# protections_1.net
KiCad netlist of a schematic drawn in Altium Designer
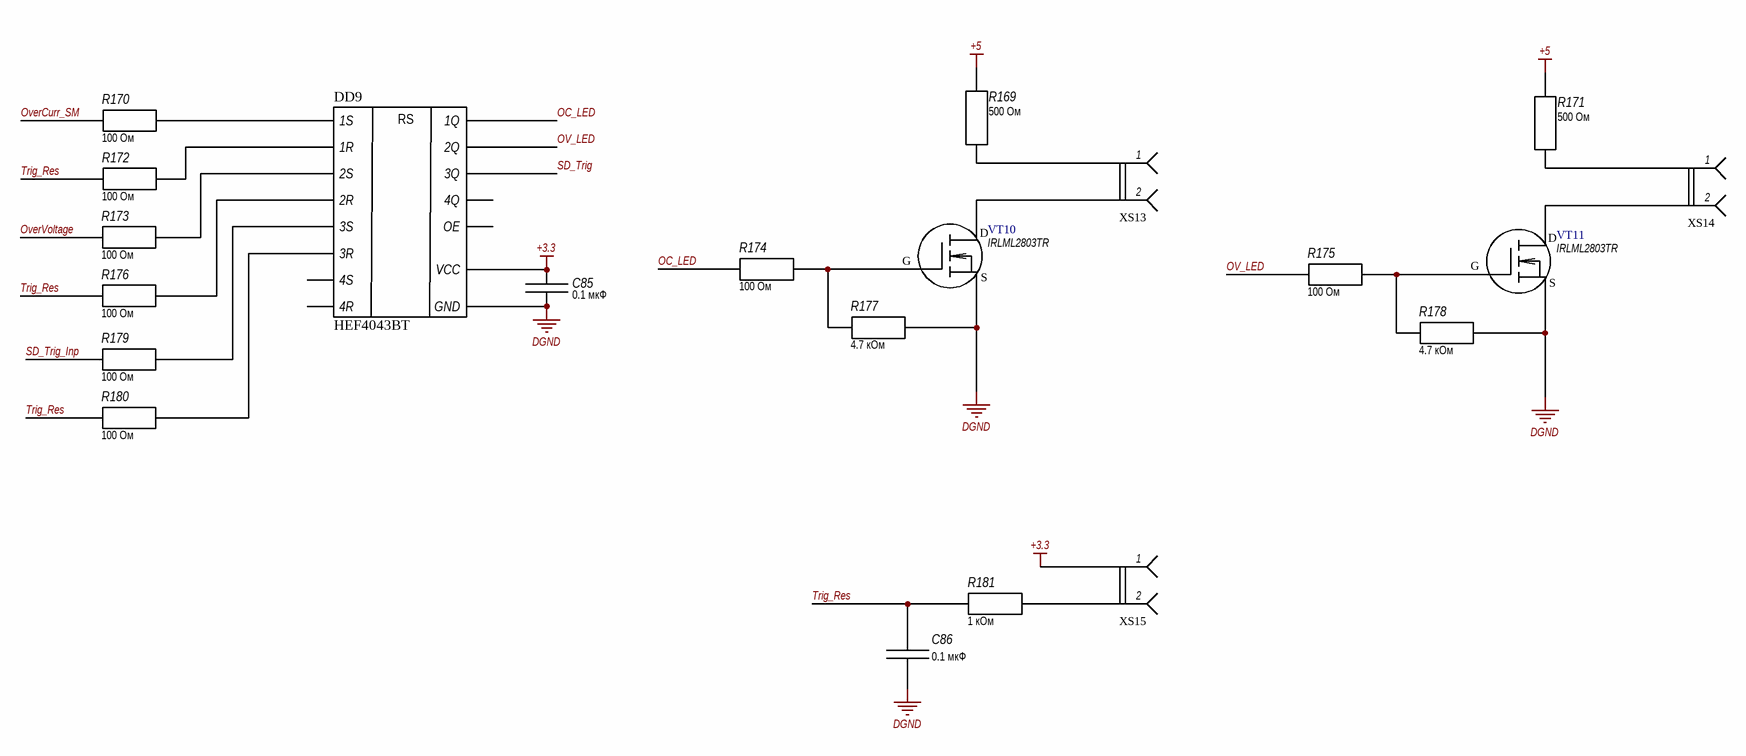
[diagram p0: protections_1.SchDoc]

(export (version "E")
  (design (tool "Eeschema 10.0.6"))
  (components
    (comp (ref "C85")
      (value "0.1 мкФ")
      (footprint "CC0603")
      (fields (field (name "VOLTAGE") "16В") (field (name "Comment") "Capacitor"))
      (libsource (lib "Main_components") (part "Capacitor"))
    )
    (comp (ref "C86")
      (value "0.1 мкФ")
      (footprint "CC0603")
      (fields (field (name "VOLTAGE") "50 В") (field (name "Comment") "Capacitor"))
      (libsource (lib "Main_components") (part "Capacitor"))
    )
    (comp (ref "DD9")
      (value "HEF4043BT")
      (footprint "SO16")
      (description "Триггер RS-типа х 4 [SOIC-16]")
      (libsource (lib "Microcircuits") (part "HEF4043BT"))
    )
    (comp (ref "R169")
      (value "500 Ом")
      (footprint "RC1206")
      (fields (field (name "POWER") "250 мВт") (field (name "Comment") "Resistor"))
      (libsource (lib "Main_components") (part "Resistor"))
    )
    (comp (ref "R170")
      (value "100 Ом")
      (footprint "RC0603")
      (fields (field (name "POWER") "100 мВт") (field (name "Comment") "Resistor"))
      (libsource (lib "Main_components") (part "Resistor"))
    )
    (comp (ref "R171")
      (value "500 Ом")
      (footprint "RC1206")
      (fields (field (name "POWER") "250 мВт") (field (name "Comment") "Resistor"))
      (libsource (lib "Main_components") (part "Resistor"))
    )
    (comp (ref "R172")
      (value "100 Ом")
      (footprint "RC0603")
      (fields (field (name "POWER") "100 мВт") (field (name "Comment") "Resistor"))
      (libsource (lib "Main_components") (part "Resistor"))
    )
    (comp (ref "R173")
      (value "100 Ом")
      (footprint "RC0603")
      (fields (field (name "POWER") "100 мВт") (field (name "Comment") "Resistor"))
      (libsource (lib "Main_components") (part "Resistor"))
    )
    (comp (ref "R174")
      (value "100 Ом")
      (footprint "RC0603")
      (fields (field (name "POWER") "100 мВт") (field (name "Comment") "Resistor"))
      (libsource (lib "Main_components") (part "Resistor"))
    )
    (comp (ref "R175")
      (value "100 Ом")
      (footprint "RC0603")
      (fields (field (name "POWER") "100 мВт") (field (name "Comment") "Resistor"))
      (libsource (lib "Main_components") (part "Resistor"))
    )
    (comp (ref "R176")
      (value "100 Ом")
      (footprint "RC0603")
      (fields (field (name "POWER") "100 мВт") (field (name "Comment") "Resistor"))
      (libsource (lib "Main_components") (part "Resistor"))
    )
    (comp (ref "R177")
      (value "4.7 кОм")
      (footprint "RC0603")
      (fields (field (name "POWER") "100 мВт") (field (name "Comment") "Resistor"))
      (libsource (lib "Main_components") (part "Resistor"))
    )
    (comp (ref "R178")
      (value "4.7 кОм")
      (footprint "RC0603")
      (fields (field (name "POWER") "100 мВт") (field (name "Comment") "Resistor"))
      (libsource (lib "Main_components") (part "Resistor"))
    )
    (comp (ref "R179")
      (value "100 Ом")
      (footprint "RC0603")
      (fields (field (name "POWER") "100 мВт") (field (name "Comment") "Resistor"))
      (libsource (lib "Main_components") (part "Resistor"))
    )
    (comp (ref "R180")
      (value "100 Ом")
      (footprint "RC0603")
      (fields (field (name "POWER") "100 мВт") (field (name "Comment") "Resistor"))
      (libsource (lib "Main_components") (part "Resistor"))
    )
    (comp (ref "R181")
      (value "1 кОм")
      (footprint "RC0603")
      (fields (field (name "POWER") "100 мВт") (field (name "Comment") "Resistor"))
      (libsource (lib "Main_components") (part "Resistor"))
    )
    (comp (ref "VT10")
      (value "IRLML2803TR")
      (footprint "SOT-23-3")
      (libsource (lib "Main_components") (part "N-MOSFET"))
    )
    (comp (ref "VT11")
      (value "IRLML2803TR")
      (footprint "SOT-23-3")
      (libsource (lib "Main_components") (part "N-MOSFET"))
    )
    (comp (ref "XS13")
      (value "JST-Male-2")
      (footprint "JST-2")
      (libsource (lib "Connectors") (part "JST-Male-2"))
    )
    (comp (ref "XS14")
      (value "JST-Male-2")
      (footprint "JST-2")
      (libsource (lib "Connectors") (part "JST-Male-2"))
    )
    (comp (ref "XS15")
      (value "JST-Male-2")
      (footprint "JST-2")
      (libsource (lib "Connectors") (part "JST-Male-2"))
    )
  )
  (nets
    (net (code "1") (name "+3.3") (class "Default")
      (node (ref "C85") (pin "2") (pinfunction "2_2") (pintype "passive"))
      (node (ref "DD9") (pin "16") (pinfunction "VCC_16") (pintype "passive"))
      (node (ref "XS15") (pin "1") (pinfunction "1_1") (pintype "passive"))
    )
    (net (code "2") (name "+5") (class "Default")
      (node (ref "R169") (pin "1") (pinfunction "1_1") (pintype "passive"))
      (node (ref "R171") (pin "1") (pinfunction "1_1") (pintype "passive"))
    )
    (net (code "3") (name "/OC_LED") (class "Default")
      (node (ref "DD9") (pin "2") (pinfunction "1Q_2") (pintype "passive"))
      (node (ref "R174") (pin "2") (pinfunction "2_2") (pintype "passive"))
    )
    (net (code "4") (name "/OV_LED") (class "Default")
      (node (ref "DD9") (pin "9") (pinfunction "2Q_9") (pintype "passive"))
      (node (ref "R175") (pin "2") (pinfunction "2_2") (pintype "passive"))
    )
    (net (code "5") (name "/OverCurr_SM") (class "Default")
      (node (ref "R170") (pin "2") (pinfunction "2_2") (pintype "passive"))
    )
    (net (code "6") (name "/OverVoltage") (class "Default")
      (node (ref "R173") (pin "2") (pinfunction "2_2") (pintype "passive"))
    )
    (net (code "7") (name "/SD_Trig") (class "Default")
      (node (ref "DD9") (pin "10") (pinfunction "3Q_10") (pintype "passive"))
    )
    (net (code "8") (name "/SD_Trig_Inp") (class "Default")
      (node (ref "R179") (pin "2") (pinfunction "2_2") (pintype "passive"))
    )
    (net (code "9") (name "/Trig_Res") (class "Default")
      (node (ref "C86") (pin "2") (pinfunction "2_2") (pintype "passive"))
      (node (ref "R172") (pin "2") (pinfunction "2_2") (pintype "passive"))
      (node (ref "R176") (pin "2") (pinfunction "2_2") (pintype "passive"))
      (node (ref "R180") (pin "2") (pinfunction "2_2") (pintype "passive"))
      (node (ref "R181") (pin "1") (pinfunction "1_1") (pintype "passive"))
    )
    (net (code "10") (name "DGND") (class "Default")
      (node (ref "C85") (pin "1") (pinfunction "1_1") (pintype "passive"))
      (node (ref "C86") (pin "1") (pinfunction "1_1") (pintype "passive"))
      (node (ref "DD9") (pin "8") (pinfunction "GND_8") (pintype "passive"))
      (node (ref "R177") (pin "1") (pinfunction "1_1") (pintype "passive"))
      (node (ref "R178") (pin "1") (pinfunction "1_1") (pintype "passive"))
      (node (ref "VT10") (pin "S") (pinfunction "S_S") (pintype "passive"))
      (node (ref "VT11") (pin "S") (pinfunction "S_S") (pintype "passive"))
    )
    (net (code "11") (name "Net-(DD9-1R)") (class "Default")
      (node (ref "DD9") (pin "3") (pinfunction "1R_3") (pintype "passive"))
      (node (ref "R172") (pin "1") (pinfunction "1_1") (pintype "passive"))
    )
    (net (code "12") (name "Net-(DD9-1S)") (class "Default")
      (node (ref "DD9") (pin "4") (pinfunction "1S_4") (pintype "passive"))
      (node (ref "R170") (pin "1") (pinfunction "1_1") (pintype "passive"))
    )
    (net (code "13") (name "Net-(DD9-2R)") (class "Default")
      (node (ref "DD9") (pin "7") (pinfunction "2R_7") (pintype "passive"))
      (node (ref "R176") (pin "1") (pinfunction "1_1") (pintype "passive"))
    )
    (net (code "14") (name "Net-(DD9-2S)") (class "Default")
      (node (ref "DD9") (pin "6") (pinfunction "2S_6") (pintype "passive"))
      (node (ref "R173") (pin "1") (pinfunction "1_1") (pintype "passive"))
    )
    (net (code "15") (name "Net-(DD9-3R)") (class "Default")
      (node (ref "DD9") (pin "11") (pinfunction "3R_11") (pintype "passive"))
      (node (ref "R180") (pin "1") (pinfunction "1_1") (pintype "passive"))
    )
    (net (code "16") (name "Net-(DD9-3S)") (class "Default")
      (node (ref "DD9") (pin "12") (pinfunction "3S_12") (pintype "passive"))
      (node (ref "R179") (pin "1") (pinfunction "1_1") (pintype "passive"))
    )
    (net (code "17") (name "Net-(R169-Pad2)") (class "Default")
      (node (ref "R169") (pin "2") (pinfunction "2_2") (pintype "passive"))
      (node (ref "XS13") (pin "1") (pinfunction "1_1") (pintype "passive"))
    )
    (net (code "18") (name "Net-(R171-Pad2)") (class "Default")
      (node (ref "R171") (pin "2") (pinfunction "2_2") (pintype "passive"))
      (node (ref "XS14") (pin "1") (pinfunction "1_1") (pintype "passive"))
    )
    (net (code "19") (name "Net-(R174-Pad1)") (class "Default")
      (node (ref "R174") (pin "1") (pinfunction "1_1") (pintype "passive"))
      (node (ref "R177") (pin "2") (pinfunction "2_2") (pintype "passive"))
      (node (ref "VT10") (pin "G") (pinfunction "G_G") (pintype "passive"))
    )
    (net (code "20") (name "Net-(R175-Pad1)") (class "Default")
      (node (ref "R175") (pin "1") (pinfunction "1_1") (pintype "passive"))
      (node (ref "R178") (pin "2") (pinfunction "2_2") (pintype "passive"))
      (node (ref "VT11") (pin "G") (pinfunction "G_G") (pintype "passive"))
    )
    (net (code "21") (name "Net-(R181-Pad2)") (class "Default")
      (node (ref "R181") (pin "2") (pinfunction "2_2") (pintype "passive"))
      (node (ref "XS15") (pin "2") (pinfunction "2_2") (pintype "passive"))
    )
    (net (code "22") (name "Net-(VT10-PadD)") (class "Default")
      (node (ref "VT10") (pin "D") (pinfunction "D_D") (pintype "passive"))
      (node (ref "XS13") (pin "2") (pinfunction "2_2") (pintype "passive"))
    )
    (net (code "23") (name "Net-(VT11-PadD)") (class "Default")
      (node (ref "VT11") (pin "D") (pinfunction "D_D") (pintype "passive"))
      (node (ref "XS14") (pin "2") (pinfunction "2_2") (pintype "passive"))
    )
    (net (code "24") (name "unconnected-(DD9-4Q-Pad1)") (class "Default")
      (node (ref "DD9") (pin "1") (pinfunction "4Q_1") (pintype "passive"))
    )
    (net (code "25") (name "unconnected-(DD9-4R-Pad15)") (class "Default")
      (node (ref "DD9") (pin "15") (pinfunction "4R_15") (pintype "passive"))
    )
    (net (code "26") (name "unconnected-(DD9-4S-Pad14)") (class "Default")
      (node (ref "DD9") (pin "14") (pinfunction "4S_14") (pintype "passive"))
    )
    (net (code "27") (name "unconnected-(DD9-OE-Pad5)") (class "Default")
      (node (ref "DD9") (pin "5") (pinfunction "OE_5") (pintype "passive"))
    )
  )
)
